# IR_V2.net
KiCad netlist of a schematic drawn in Altium Designer
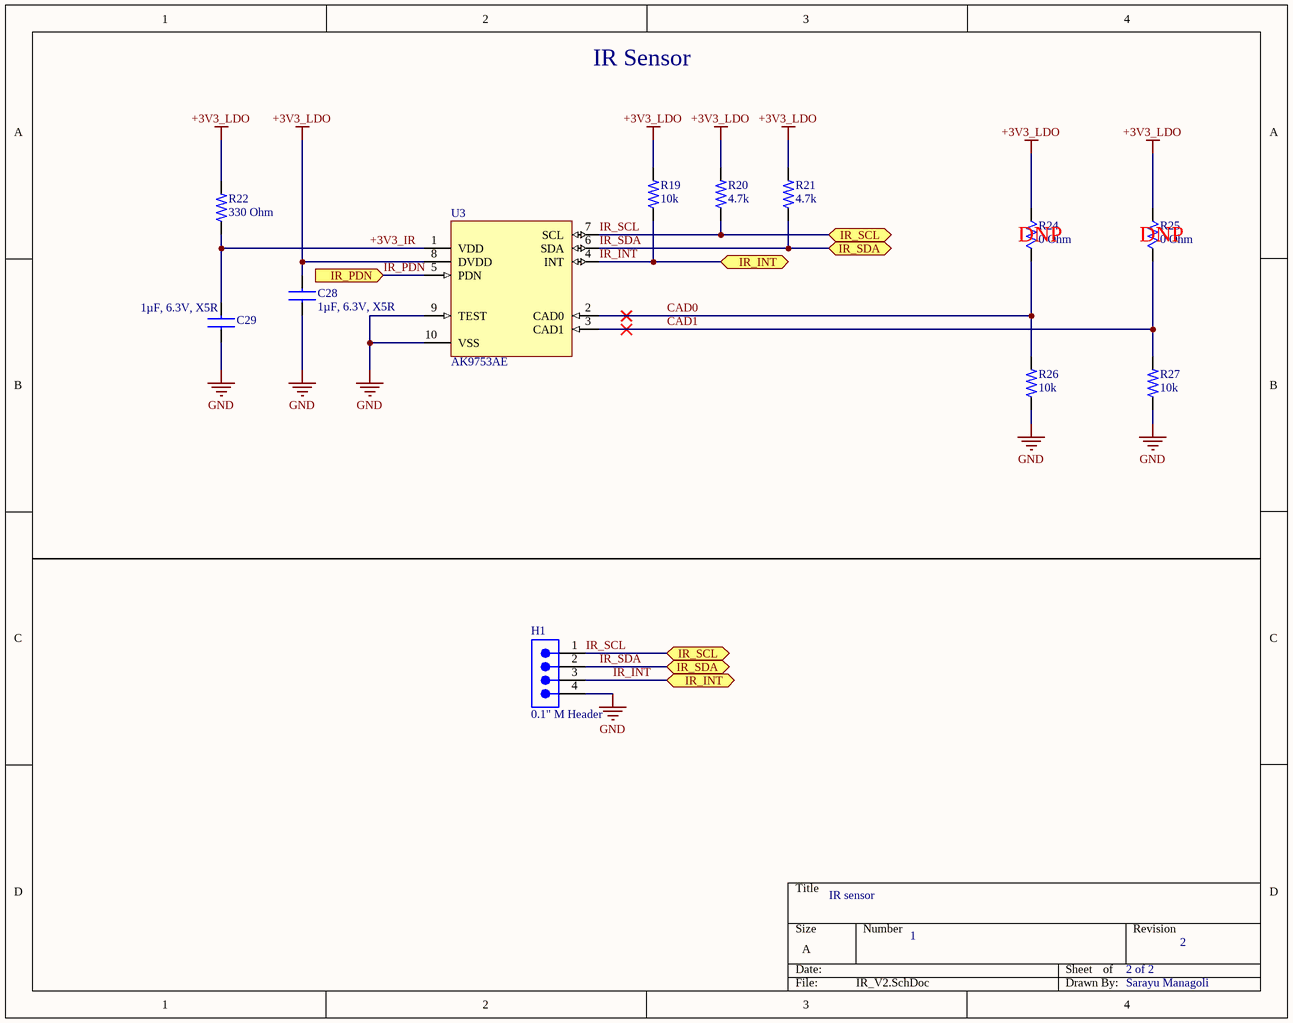
[diagram p0: IR_V2.SchDoc]

(export (version "E")
  (design (tool "Eeschema 10.0.6"))
  (components
    (comp (ref "C28")
      (value "1µF, 6.3V, X5R")
      (footprint "CAPC2012X14N")
      (description "CAP CER 1UF 6.3V X5R 0805")
      (fields
        (field (name "MANUFACTURER") "Yageo")
        (field (name "MANUFACTURER PART NUMBER") "CC0805KKX5R5BB105")
      )
      (libsource (lib "PMIC_IR") (part "CC0805KKX5R5BB105"))
    )
    (comp (ref "C29")
      (value "1µF, 6.3V, X5R")
      (footprint "CAPC2012X14N")
      (description "CAP CER 1UF 6.3V X5R 0805")
      (fields
        (field (name "MANUFACTURER") "Yageo")
        (field (name "MANUFACTURER PART NUMBER") "CC0805KKX5R5BB105")
      )
      (libsource (lib "PMIC_IR") (part "CC0805KKX5R5BB105"))
    )
    (comp (ref "H1")
      (value "0.1\" M Header")
      (footprint "4-PIN_MALE_HEADER_01-IN")
      (description "CONN HEADER VERT 4POS 2.54MM")
      (fields
        (field (name "MANUFACTURER") "Sullins")
        (field (name "MANUFACTURER PART NUMBER") "PRPC004SAAN-RC")
      )
      (libsource (lib "PMIC_IR") (part "PRPC004SAAN-RC"))
    )
    (comp (ref "R19")
      (value "10k")
      (footprint "RESC1508X06N_10K")
      (description "Res Thin Film 0603 10K Ohm 1% 1/16W ±50ppm/°C Molded SMD SMD Paper T/R")
      (fields
        (field (name "MANUFACTURER") "TE Connectivity Neohm")
        (field (name "MANUFACTURER PART NUMBER") "CPF0603F10KC1")
      )
      (libsource (lib "PMIC_IR") (part "CPF0603F10KC1"))
    )
    (comp (ref "R20")
      (value "4.7k")
      (footprint "RESC1608X06N_4_7")
      (description "RES SMD 4.7K OHM 1% 1/8W 0603")
      (fields
        (field (name "MANUFACTURER") "Vishay Beyschlag")
        (field (name "MANUFACTURER PART NUMBER") "MCT06030C4701FP500")
      )
      (libsource (lib "PMIC_IR") (part "MCT06030C4701FP500"))
    )
    (comp (ref "R21")
      (value "4.7k")
      (footprint "RESC1608X06N_4_7")
      (description "RES SMD 4.7K OHM 1% 1/8W 0603")
      (fields
        (field (name "MANUFACTURER") "Vishay Beyschlag")
        (field (name "MANUFACTURER PART NUMBER") "MCT06030C4701FP500")
      )
      (libsource (lib "PMIC_IR") (part "MCT06030C4701FP500"))
    )
    (comp (ref "R22")
      (value "330 Ohm")
      (footprint "RESC1608X06N_330")
      (description "RES SMD 0603 1/4W 1% 330 OHM")
      (fields
        (field (name "MANUFACTURER") "Yageo")
        (field (name "MANUFACTURER PART NUMBER") "SR0603FR-7T330RL")
      )
      (libsource (lib "PMIC_IR") (part "SR0603FR-7T330RL"))
    )
    (comp (ref "R24")
      (value "0 Ohm")
      (footprint "RES_0_0603")
      (description "Jumper, 0 ohm, 0603 [Metrisch 1608], Baureihe RC, 75 V, Dickschicht")
      (fields
        (field (name "MANUFACTURER") "Yageo")
        (field (name "MANUFACTURER PART NUMBER") "RC0603JR-070RL")
      )
      (libsource (lib "PMIC_IR") (part "RC0603JR-070RL"))
    )
    (comp (ref "R25")
      (value "0 Ohm")
      (footprint "RES_0_0603")
      (description "Jumper, 0 ohm, 0603 [Metrisch 1608], Baureihe RC, 75 V, Dickschicht")
      (fields
        (field (name "MANUFACTURER") "Yageo")
        (field (name "MANUFACTURER PART NUMBER") "RC0603JR-070RL")
      )
      (libsource (lib "PMIC_IR") (part "RC0603JR-070RL"))
    )
    (comp (ref "R26")
      (value "10k")
      (footprint "RESC1508X06N_10K")
      (description "Res Thin Film 0603 10K Ohm 1% 1/16W ±50ppm/°C Molded SMD SMD Paper T/R")
      (fields
        (field (name "MANUFACTURER") "TE Connectivity Neohm")
        (field (name "MANUFACTURER PART NUMBER") "CPF0603F10KC1")
      )
      (libsource (lib "PMIC_IR") (part "CPF0603F10KC1"))
    )
    (comp (ref "R27")
      (value "10k")
      (footprint "RESC1508X06N_10K")
      (description "Res Thin Film 0603 10K Ohm 1% 1/16W ±50ppm/°C Molded SMD SMD Paper T/R")
      (fields
        (field (name "MANUFACTURER") "TE Connectivity Neohm")
        (field (name "MANUFACTURER PART NUMBER") "CPF0603F10KC1")
      )
      (libsource (lib "PMIC_IR") (part "CPF0603F10KC1"))
    )
    (comp (ref "U3")
      (value "AK9753AE")
      (footprint "SON65P460X114-10N")
      (description "IC 4CH IR SENSOR I2C 10SON")
      (fields (field (name "MANUFACTURER") "AKM Semiconductor"))
      (libsource (lib "PMIC_IR") (part "AK9753AE"))
    )
  )
  (nets
    (net (code "1") (name "+3V3_LDO") (class "Default")
      (node (ref "C28") (pin "1") (pinfunction "1_1") (pintype "passive"))
      (node (ref "R19") (pin "2") (pinfunction "2_2") (pintype "passive"))
      (node (ref "R20") (pin "2") (pinfunction "2_2") (pintype "passive"))
      (node (ref "R21") (pin "2") (pinfunction "2_2") (pintype "passive"))
      (node (ref "R22") (pin "2") (pinfunction "2_2") (pintype "passive"))
      (node (ref "R24") (pin "2") (pinfunction "2_2") (pintype "passive"))
      (node (ref "R25") (pin "2") (pinfunction "2_2") (pintype "passive"))
      (node (ref "U3") (pin "8") (pinfunction "DVDD_8") (pintype "power_in"))
    )
    (net (code "2") (name "/+3V3_IR") (class "Default")
      (node (ref "C29") (pin "1") (pinfunction "1_1") (pintype "passive"))
      (node (ref "R22") (pin "1") (pinfunction "1_1") (pintype "passive"))
      (node (ref "U3") (pin "1") (pinfunction "VDD_1") (pintype "power_in"))
    )
    (net (code "3") (name "/CAD0") (class "Default")
      (node (ref "R24") (pin "1") (pinfunction "1_1") (pintype "passive"))
      (node (ref "R26") (pin "2") (pinfunction "2_2") (pintype "passive"))
      (node (ref "U3") (pin "2") (pinfunction "CAD0_2") (pintype "input"))
    )
    (net (code "4") (name "/CAD1") (class "Default")
      (node (ref "R25") (pin "1") (pinfunction "1_1") (pintype "passive"))
      (node (ref "R27") (pin "2") (pinfunction "2_2") (pintype "passive"))
      (node (ref "U3") (pin "3") (pinfunction "CAD1_3") (pintype "input"))
    )
    (net (code "5") (name "/IR_INT") (class "Default")
      (node (ref "H1") (pin "3") (pinfunction "3_3") (pintype "passive"))
      (node (ref "R19") (pin "1") (pinfunction "1_1") (pintype "passive"))
      (node (ref "U3") (pin "4") (pinfunction "INT_4") (pintype "bidirectional"))
    )
    (net (code "6") (name "/IR_PDN") (class "Default")
      (node (ref "U3") (pin "5") (pinfunction "PDN_5") (pintype "input"))
    )
    (net (code "7") (name "/IR_SCL") (class "Default")
      (node (ref "H1") (pin "1") (pinfunction "1_1") (pintype "passive"))
      (node (ref "R20") (pin "1") (pinfunction "1_1") (pintype "passive"))
      (node (ref "U3") (pin "7") (pinfunction "SCL_7") (pintype "bidirectional"))
    )
    (net (code "8") (name "/IR_SDA") (class "Default")
      (node (ref "H1") (pin "2") (pinfunction "2_2") (pintype "passive"))
      (node (ref "R21") (pin "1") (pinfunction "1_1") (pintype "passive"))
      (node (ref "U3") (pin "6") (pinfunction "SDA_6") (pintype "bidirectional"))
    )
    (net (code "9") (name "GND") (class "Default")
      (node (ref "C28") (pin "2") (pinfunction "2_2") (pintype "passive"))
      (node (ref "C29") (pin "2") (pinfunction "2_2") (pintype "passive"))
      (node (ref "H1") (pin "4") (pinfunction "4_4") (pintype "passive"))
      (node (ref "R26") (pin "1") (pinfunction "1_1") (pintype "passive"))
      (node (ref "R27") (pin "1") (pinfunction "1_1") (pintype "passive"))
      (node (ref "U3") (pin "10") (pinfunction "VSS_10") (pintype "power_in"))
      (node (ref "U3") (pin "9") (pinfunction "TEST_9") (pintype "input"))
    )
  )
)
